# MOD-Z_01_V01.net
KiCad netlist of a schematic drawn in EAGLE
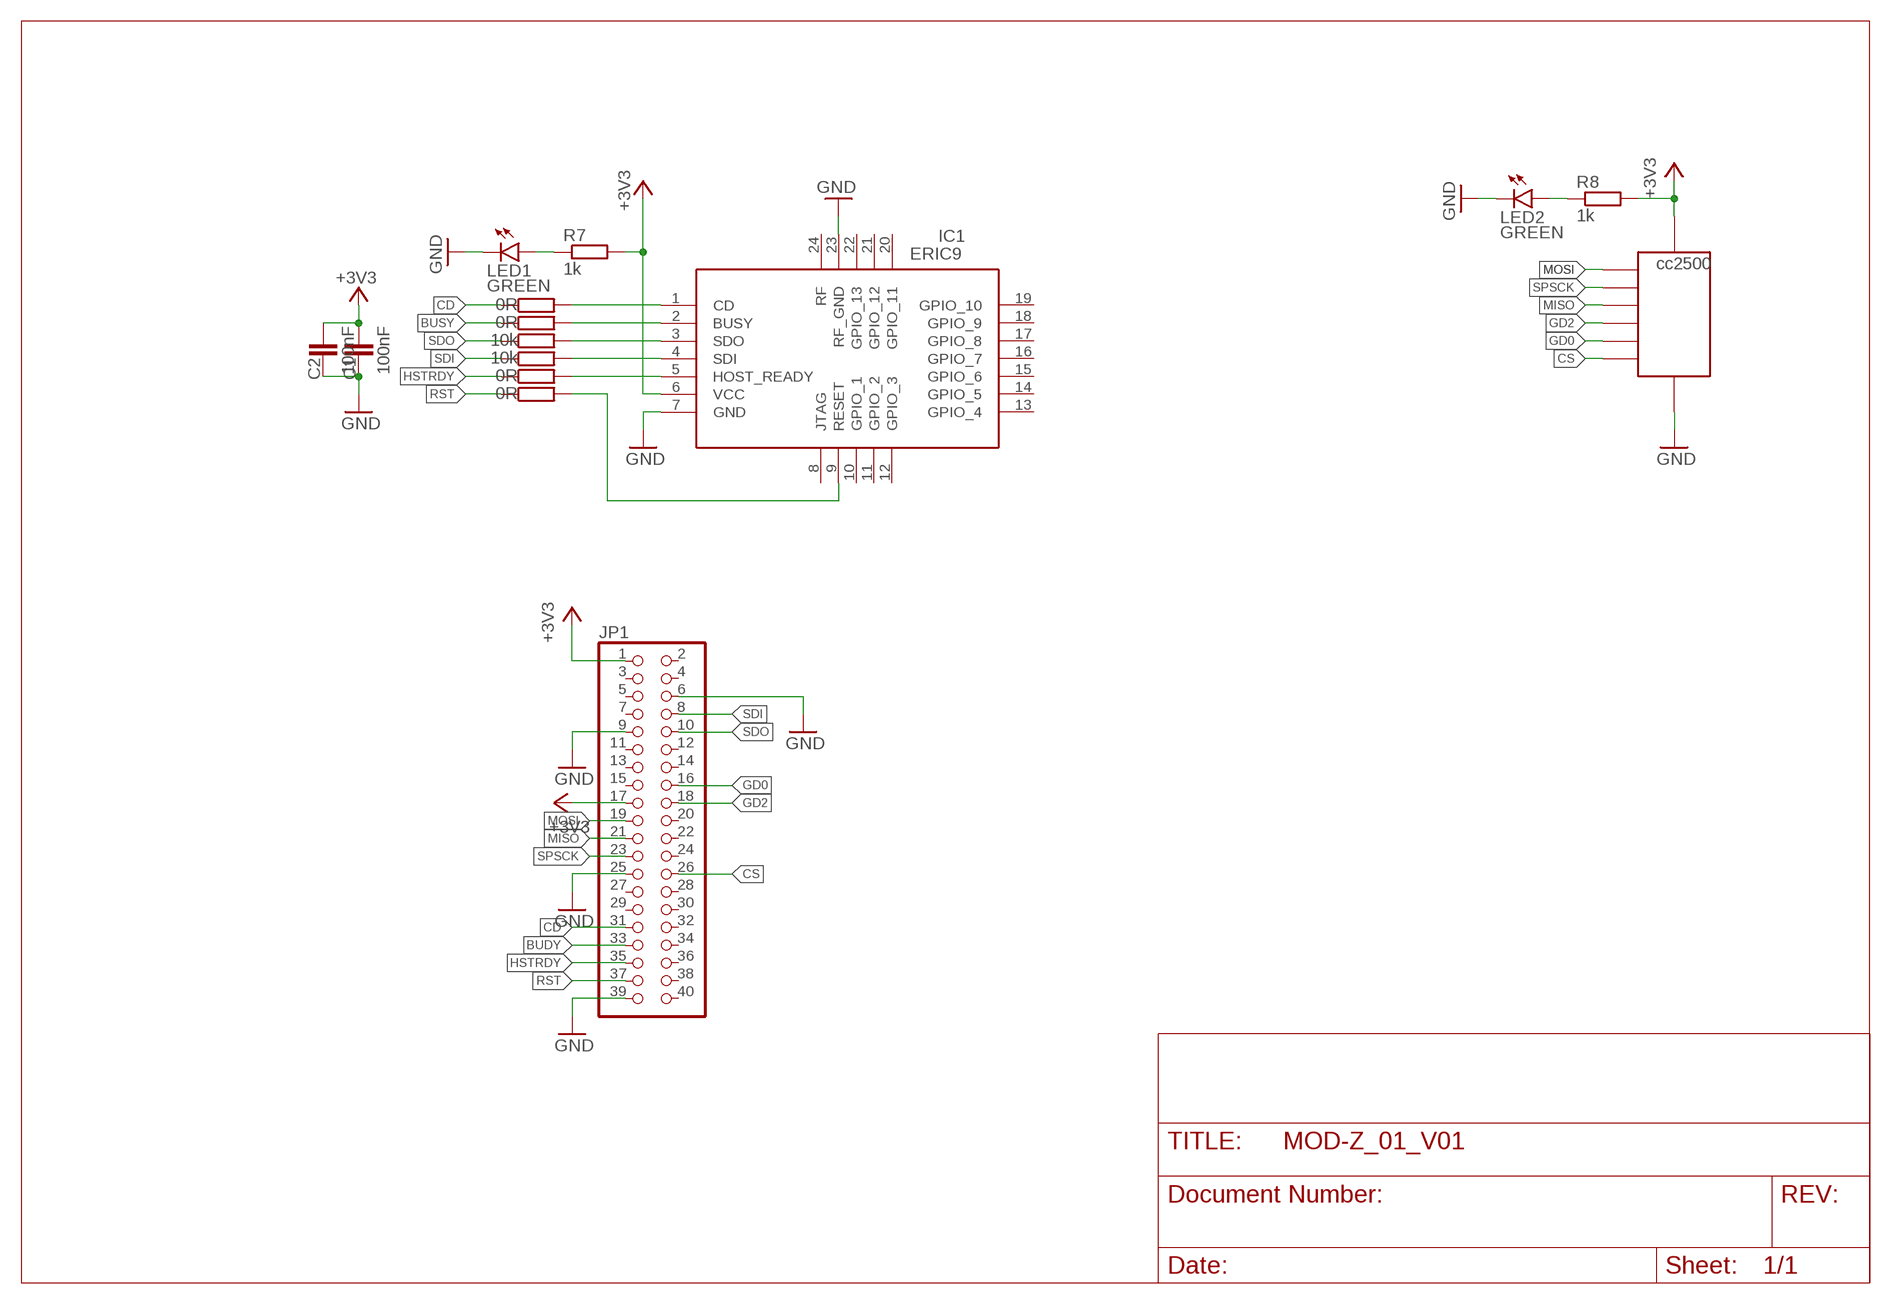
[diagram p0: schematic, sheet 1]

(export (version "E")
  (design (tool "Eeschema 10.0.6"))
  (components
    (comp (ref "C1")
      (value "100nF")
      (footprint "eagle-import:C0805")
      (libsource (lib "eagle-import") (part "C-EUC0805"))
    )
    (comp (ref "C2")
      (value "100nF")
      (footprint "eagle-import:C0805")
      (libsource (lib "eagle-import") (part "C-EUC0805"))
    )
    (comp (ref "IC1")
      (value "ERIC9")
      (footprint "eagle-import:ERIC9")
      (fields (field (name "MANUFACTURER_PART_NUMBER") "eRIC9"))
      (libsource (lib "eagle-import") (part "ERIC9"))
    )
    (comp (ref "IC2")
      (value "CC2500")
      (footprint "eagle-import:CC2500")
      (libsource (lib "eagle-import") (part "CC2500"))
    )
    (comp (ref "JP1")
      (value "PINHD-2X20")
      (footprint "eagle-import:2X20")
      (libsource (lib "eagle-import") (part "PINHD-2X20"))
    )
    (comp (ref "LED1")
      (value "GREEN")
      (footprint "eagle-import:CHIP-LED0805")
      (libsource (lib "eagle-import") (part "LEDCHIP-LED0805"))
    )
    (comp (ref "LED2")
      (value "GREEN")
      (footprint "eagle-import:CHIP-LED0805")
      (libsource (lib "eagle-import") (part "LEDCHIP-LED0805"))
    )
    (comp (ref "R1")
      (value "0R")
      (footprint "eagle-import:R0805")
      (libsource (lib "eagle-import") (part "R-EU_R0805"))
    )
    (comp (ref "R2")
      (value "0R")
      (footprint "eagle-import:R0805")
      (libsource (lib "eagle-import") (part "R-EU_R0805"))
    )
    (comp (ref "R3")
      (value "10k")
      (footprint "eagle-import:R0805")
      (libsource (lib "eagle-import") (part "R-EU_R0805"))
    )
    (comp (ref "R4")
      (value "10k")
      (footprint "eagle-import:R0805")
      (libsource (lib "eagle-import") (part "R-EU_R0805"))
    )
    (comp (ref "R5")
      (value "0R")
      (footprint "eagle-import:R0805")
      (libsource (lib "eagle-import") (part "R-EU_R0805"))
    )
    (comp (ref "R6")
      (value "0R")
      (footprint "eagle-import:R0805")
      (libsource (lib "eagle-import") (part "R-EU_R0805"))
    )
    (comp (ref "R7")
      (value "1k")
      (footprint "eagle-import:R0805")
      (libsource (lib "eagle-import") (part "R-EU_R0805"))
    )
    (comp (ref "R8")
      (value "1k")
      (footprint "eagle-import:R0805")
      (libsource (lib "eagle-import") (part "R-EU_R0805"))
    )
  )
  (nets
    (net (code "1") (name "+3V3") (class "Default")
      (node (ref "C1") (pin "1") (pinfunction "1_1") (pintype "passive"))
      (node (ref "C2") (pin "1") (pinfunction "1_1") (pintype "passive"))
      (node (ref "IC1") (pin "6") (pinfunction "VCC_6") (pintype "bidirectional"))
      (node (ref "IC2") (pin "+3V3") (pinfunction "+3V3_+3V3") (pintype "power_in"))
      (node (ref "JP1") (pin "1") (pinfunction "1_1") (pintype "passive"))
      (node (ref "JP1") (pin "17") (pinfunction "17_17") (pintype "passive"))
      (node (ref "R7") (pin "2") (pinfunction "2_2") (pintype "passive"))
      (node (ref "R8") (pin "2") (pinfunction "2_2") (pintype "passive"))
    )
    (net (code "2") (name "BUDY") (class "Default")
      (node (ref "JP1") (pin "33") (pinfunction "33_33") (pintype "passive"))
    )
    (net (code "3") (name "BUSY") (class "Default")
      (node (ref "R2") (pin "1") (pinfunction "1_1") (pintype "passive"))
    )
    (net (code "4") (name "CD") (class "Default")
      (node (ref "JP1") (pin "31") (pinfunction "31_31") (pintype "passive"))
      (node (ref "R1") (pin "1") (pinfunction "1_1") (pintype "passive"))
    )
    (net (code "5") (name "CS") (class "Default")
      (node (ref "IC2") (pin "CS") (pinfunction "CS_CS") (pintype "bidirectional"))
      (node (ref "JP1") (pin "26") (pinfunction "26_26") (pintype "passive"))
    )
    (net (code "6") (name "GD0") (class "Default")
      (node (ref "IC2") (pin "SPSCK") (pinfunction "SPSCK_SPSCK") (pintype "bidirectional"))
      (node (ref "JP1") (pin "16") (pinfunction "16_16") (pintype "passive"))
    )
    (net (code "7") (name "GD2") (class "Default")
      (node (ref "IC2") (pin "MOSI") (pinfunction "MOSI_MOSI") (pintype "bidirectional"))
      (node (ref "JP1") (pin "18") (pinfunction "18_18") (pintype "passive"))
    )
    (net (code "8") (name "GND") (class "Default")
      (node (ref "C1") (pin "2") (pinfunction "2_2") (pintype "passive"))
      (node (ref "C2") (pin "2") (pinfunction "2_2") (pintype "passive"))
      (node (ref "IC1") (pin "23") (pinfunction "RF_GND_23") (pintype "bidirectional"))
      (node (ref "IC1") (pin "7") (pinfunction "GND_7") (pintype "bidirectional"))
      (node (ref "IC2") (pin "GND") (pinfunction "GND_GND") (pintype "power_in"))
      (node (ref "JP1") (pin "25") (pinfunction "25_25") (pintype "passive"))
      (node (ref "JP1") (pin "39") (pinfunction "39_39") (pintype "passive"))
      (node (ref "JP1") (pin "6") (pinfunction "6_6") (pintype "passive"))
      (node (ref "JP1") (pin "9") (pinfunction "9_9") (pintype "passive"))
      (node (ref "LED1") (pin "C") (pinfunction "C_C") (pintype "passive"))
      (node (ref "LED2") (pin "C") (pinfunction "C_C") (pintype "passive"))
    )
    (net (code "9") (name "HSTRDY") (class "Default")
      (node (ref "JP1") (pin "35") (pinfunction "35_35") (pintype "passive"))
      (node (ref "R5") (pin "1") (pinfunction "1_1") (pintype "passive"))
    )
    (net (code "10") (name "MISO") (class "Default")
      (node (ref "IC2") (pin "MISO") (pinfunction "MISO_MISO") (pintype "bidirectional"))
      (node (ref "JP1") (pin "21") (pinfunction "21_21") (pintype "passive"))
    )
    (net (code "11") (name "MOSI") (class "Default")
      (node (ref "IC2") (pin "GD0") (pinfunction "GD0_GD0") (pintype "bidirectional"))
      (node (ref "JP1") (pin "19") (pinfunction "19_19") (pintype "passive"))
    )
    (net (code "12") (name "Net-(IC1-BUSY)") (class "Default")
      (node (ref "IC1") (pin "2") (pinfunction "BUSY_2") (pintype "bidirectional"))
      (node (ref "R2") (pin "2") (pinfunction "2_2") (pintype "passive"))
    )
    (net (code "13") (name "Net-(IC1-CD)") (class "Default")
      (node (ref "IC1") (pin "1") (pinfunction "CD_1") (pintype "bidirectional"))
      (node (ref "R1") (pin "2") (pinfunction "2_2") (pintype "passive"))
    )
    (net (code "14") (name "Net-(IC1-HOST_READY)") (class "Default")
      (node (ref "IC1") (pin "5") (pinfunction "HOST_READY_5") (pintype "bidirectional"))
      (node (ref "R5") (pin "2") (pinfunction "2_2") (pintype "passive"))
    )
    (net (code "15") (name "Net-(IC1-RESET)") (class "Default")
      (node (ref "IC1") (pin "9") (pinfunction "RESET_9") (pintype "bidirectional"))
      (node (ref "R6") (pin "2") (pinfunction "2_2") (pintype "passive"))
    )
    (net (code "16") (name "Net-(IC1-SDI)") (class "Default")
      (node (ref "IC1") (pin "4") (pinfunction "SDI_4") (pintype "bidirectional"))
      (node (ref "R4") (pin "2") (pinfunction "2_2") (pintype "passive"))
    )
    (net (code "17") (name "Net-(IC1-SDO)") (class "Default")
      (node (ref "IC1") (pin "3") (pinfunction "SDO_3") (pintype "bidirectional"))
      (node (ref "R3") (pin "2") (pinfunction "2_2") (pintype "passive"))
    )
    (net (code "18") (name "Net-(LED1-PadA)") (class "Default")
      (node (ref "LED1") (pin "A") (pinfunction "A_A") (pintype "passive"))
      (node (ref "R7") (pin "1") (pinfunction "1_1") (pintype "passive"))
    )
    (net (code "19") (name "Net-(LED2-PadA)") (class "Default")
      (node (ref "LED2") (pin "A") (pinfunction "A_A") (pintype "passive"))
      (node (ref "R8") (pin "1") (pinfunction "1_1") (pintype "passive"))
    )
    (net (code "20") (name "RST") (class "Default")
      (node (ref "JP1") (pin "37") (pinfunction "37_37") (pintype "passive"))
      (node (ref "R6") (pin "1") (pinfunction "1_1") (pintype "passive"))
    )
    (net (code "21") (name "SDI") (class "Default")
      (node (ref "JP1") (pin "8") (pinfunction "8_8") (pintype "passive"))
      (node (ref "R4") (pin "1") (pinfunction "1_1") (pintype "passive"))
    )
    (net (code "22") (name "SDO") (class "Default")
      (node (ref "JP1") (pin "10") (pinfunction "10_10") (pintype "passive"))
      (node (ref "R3") (pin "1") (pinfunction "1_1") (pintype "passive"))
    )
    (net (code "23") (name "SPSCK") (class "Default")
      (node (ref "IC2") (pin "GD2") (pinfunction "GD2_GD2") (pintype "bidirectional"))
      (node (ref "JP1") (pin "23") (pinfunction "23_23") (pintype "passive"))
    )
    (net (code "24") (name "unconnected-(IC1-GPIO_1-Pad10)") (class "Default")
      (node (ref "IC1") (pin "10") (pinfunction "GPIO_1_10") (pintype "bidirectional"))
    )
    (net (code "25") (name "unconnected-(IC1-GPIO_2-Pad11)") (class "Default")
      (node (ref "IC1") (pin "11") (pinfunction "GPIO_2_11") (pintype "bidirectional"))
    )
    (net (code "26") (name "unconnected-(IC1-GPIO_3-Pad12)") (class "Default")
      (node (ref "IC1") (pin "12") (pinfunction "GPIO_3_12") (pintype "bidirectional"))
    )
    (net (code "27") (name "unconnected-(IC1-GPIO_4-Pad13)") (class "Default")
      (node (ref "IC1") (pin "13") (pinfunction "GPIO_4_13") (pintype "bidirectional"))
    )
    (net (code "28") (name "unconnected-(IC1-GPIO_5-Pad14)") (class "Default")
      (node (ref "IC1") (pin "14") (pinfunction "GPIO_5_14") (pintype "bidirectional"))
    )
    (net (code "29") (name "unconnected-(IC1-GPIO_6-Pad15)") (class "Default")
      (node (ref "IC1") (pin "15") (pinfunction "GPIO_6_15") (pintype "bidirectional"))
    )
    (net (code "30") (name "unconnected-(IC1-GPIO_7-Pad16)") (class "Default")
      (node (ref "IC1") (pin "16") (pinfunction "GPIO_7_16") (pintype "bidirectional"))
    )
    (net (code "31") (name "unconnected-(IC1-GPIO_8-Pad17)") (class "Default")
      (node (ref "IC1") (pin "17") (pinfunction "GPIO_8_17") (pintype "bidirectional"))
    )
    (net (code "32") (name "unconnected-(IC1-GPIO_9-Pad18)") (class "Default")
      (node (ref "IC1") (pin "18") (pinfunction "GPIO_9_18") (pintype "bidirectional"))
    )
    (net (code "33") (name "unconnected-(IC1-GPIO_10-Pad19)") (class "Default")
      (node (ref "IC1") (pin "19") (pinfunction "GPIO_10_19") (pintype "bidirectional"))
    )
    (net (code "34") (name "unconnected-(IC1-GPIO_11-Pad20)") (class "Default")
      (node (ref "IC1") (pin "20") (pinfunction "GPIO_11_20") (pintype "bidirectional"))
    )
    (net (code "35") (name "unconnected-(IC1-GPIO_12-Pad21)") (class "Default")
      (node (ref "IC1") (pin "21") (pinfunction "GPIO_12_21") (pintype "bidirectional"))
    )
    (net (code "36") (name "unconnected-(IC1-GPIO_13-Pad22)") (class "Default")
      (node (ref "IC1") (pin "22") (pinfunction "GPIO_13_22") (pintype "bidirectional"))
    )
    (net (code "37") (name "unconnected-(IC1-JTAG-Pad8)") (class "Default")
      (node (ref "IC1") (pin "8") (pinfunction "JTAG_8") (pintype "bidirectional"))
    )
    (net (code "38") (name "unconnected-(IC1-RF-Pad24)") (class "Default")
      (node (ref "IC1") (pin "24") (pinfunction "RF_24") (pintype "bidirectional"))
    )
    (net (code "39") (name "unconnected-(JP1-Pad2)") (class "Default")
      (node (ref "JP1") (pin "2") (pinfunction "2_2") (pintype "passive"))
    )
    (net (code "40") (name "unconnected-(JP1-Pad3)") (class "Default")
      (node (ref "JP1") (pin "3") (pinfunction "3_3") (pintype "passive"))
    )
    (net (code "41") (name "unconnected-(JP1-Pad4)") (class "Default")
      (node (ref "JP1") (pin "4") (pinfunction "4_4") (pintype "passive"))
    )
    (net (code "42") (name "unconnected-(JP1-Pad5)") (class "Default")
      (node (ref "JP1") (pin "5") (pinfunction "5_5") (pintype "passive"))
    )
    (net (code "43") (name "unconnected-(JP1-Pad7)") (class "Default")
      (node (ref "JP1") (pin "7") (pinfunction "7_7") (pintype "passive"))
    )
    (net (code "44") (name "unconnected-(JP1-Pad11)") (class "Default")
      (node (ref "JP1") (pin "11") (pinfunction "11_11") (pintype "passive"))
    )
    (net (code "45") (name "unconnected-(JP1-Pad12)") (class "Default")
      (node (ref "JP1") (pin "12") (pinfunction "12_12") (pintype "passive"))
    )
    (net (code "46") (name "unconnected-(JP1-Pad13)") (class "Default")
      (node (ref "JP1") (pin "13") (pinfunction "13_13") (pintype "passive"))
    )
    (net (code "47") (name "unconnected-(JP1-Pad14)") (class "Default")
      (node (ref "JP1") (pin "14") (pinfunction "14_14") (pintype "passive"))
    )
    (net (code "48") (name "unconnected-(JP1-Pad15)") (class "Default")
      (node (ref "JP1") (pin "15") (pinfunction "15_15") (pintype "passive"))
    )
    (net (code "49") (name "unconnected-(JP1-Pad20)") (class "Default")
      (node (ref "JP1") (pin "20") (pinfunction "20_20") (pintype "passive"))
    )
    (net (code "50") (name "unconnected-(JP1-Pad22)") (class "Default")
      (node (ref "JP1") (pin "22") (pinfunction "22_22") (pintype "passive"))
    )
    (net (code "51") (name "unconnected-(JP1-Pad24)") (class "Default")
      (node (ref "JP1") (pin "24") (pinfunction "24_24") (pintype "passive"))
    )
    (net (code "52") (name "unconnected-(JP1-Pad27)") (class "Default")
      (node (ref "JP1") (pin "27") (pinfunction "27_27") (pintype "passive"))
    )
    (net (code "53") (name "unconnected-(JP1-Pad28)") (class "Default")
      (node (ref "JP1") (pin "28") (pinfunction "28_28") (pintype "passive"))
    )
    (net (code "54") (name "unconnected-(JP1-Pad29)") (class "Default")
      (node (ref "JP1") (pin "29") (pinfunction "29_29") (pintype "passive"))
    )
    (net (code "55") (name "unconnected-(JP1-Pad30)") (class "Default")
      (node (ref "JP1") (pin "30") (pinfunction "30_30") (pintype "passive"))
    )
    (net (code "56") (name "unconnected-(JP1-Pad32)") (class "Default")
      (node (ref "JP1") (pin "32") (pinfunction "32_32") (pintype "passive"))
    )
    (net (code "57") (name "unconnected-(JP1-Pad34)") (class "Default")
      (node (ref "JP1") (pin "34") (pinfunction "34_34") (pintype "passive"))
    )
    (net (code "58") (name "unconnected-(JP1-Pad36)") (class "Default")
      (node (ref "JP1") (pin "36") (pinfunction "36_36") (pintype "passive"))
    )
    (net (code "59") (name "unconnected-(JP1-Pad38)") (class "Default")
      (node (ref "JP1") (pin "38") (pinfunction "38_38") (pintype "passive"))
    )
    (net (code "60") (name "unconnected-(JP1-Pad40)") (class "Default")
      (node (ref "JP1") (pin "40") (pinfunction "40_40") (pintype "passive"))
    )
  )
)
